# Status_LEDs.net
KiCad netlist of a schematic drawn in Altium Designer
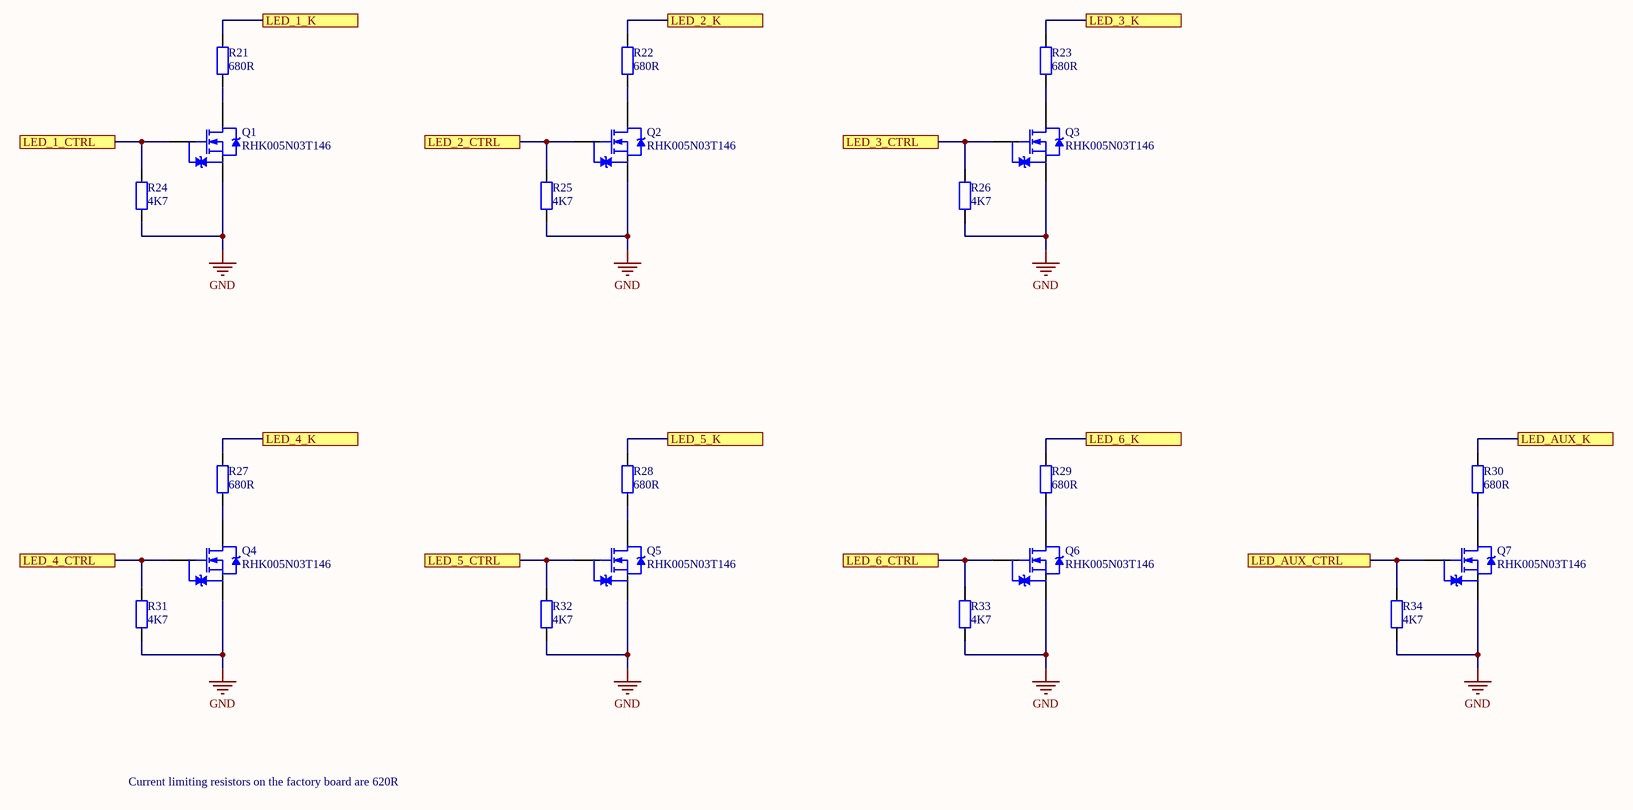
[diagram p0: Status LEDs.SchDoc]

(export (version "E")
  (design (tool "Eeschema 10.0.6"))
  (components
    (comp (ref "Q1")
      (value "RHK005N03T146")
      (footprint "RHK005N03T146 - SOT95P280X110-3N")
      (description "MOSFET N-CH 30V 500MA")
      (libsource (lib "KBuchka-IntLib") (part "RHK005N03T146"))
    )
    (comp (ref "Q2")
      (value "RHK005N03T146")
      (footprint "RHK005N03T146 - SOT95P280X110-3N")
      (description "MOSFET N-CH 30V 500MA")
      (libsource (lib "KBuchka-IntLib") (part "RHK005N03T146"))
    )
    (comp (ref "Q3")
      (value "RHK005N03T146")
      (footprint "RHK005N03T146 - SOT95P280X110-3N")
      (description "MOSFET N-CH 30V 500MA")
      (libsource (lib "KBuchka-IntLib") (part "RHK005N03T146"))
    )
    (comp (ref "Q4")
      (value "RHK005N03T146")
      (footprint "RHK005N03T146 - SOT95P280X110-3N")
      (description "MOSFET N-CH 30V 500MA")
      (libsource (lib "KBuchka-IntLib") (part "RHK005N03T146"))
    )
    (comp (ref "Q5")
      (value "RHK005N03T146")
      (footprint "RHK005N03T146 - SOT95P280X110-3N")
      (description "MOSFET N-CH 30V 500MA")
      (libsource (lib "KBuchka-IntLib") (part "RHK005N03T146"))
    )
    (comp (ref "Q6")
      (value "RHK005N03T146")
      (footprint "RHK005N03T146 - SOT95P280X110-3N")
      (description "MOSFET N-CH 30V 500MA")
      (libsource (lib "KBuchka-IntLib") (part "RHK005N03T146"))
    )
    (comp (ref "Q7")
      (value "RHK005N03T146")
      (footprint "RHK005N03T146 - SOT95P280X110-3N")
      (description "MOSFET N-CH 30V 500MA")
      (libsource (lib "KBuchka-IntLib") (part "RHK005N03T146"))
    )
    (comp (ref "R21")
      (value "680R")
      (footprint "RES_SM0603_YAGEORC_N")
      (description "RES 680R SM0603 YAGEO RC_L")
      (fields
        (field (name "MANUFACTURER") "Yageo")
        (field (name "MANUFACTURER PART NUMBER") "RC0603FR-07680RL")
      )
      (libsource (lib "Yageo") (part "RC0603FR-07680RL"))
    )
    (comp (ref "R22")
      (value "680R")
      (footprint "RES_SM0603_YAGEORC_N")
      (description "RES 680R SM0603 YAGEO RC_L")
      (fields
        (field (name "MANUFACTURER") "Yageo")
        (field (name "MANUFACTURER PART NUMBER") "RC0603FR-07680RL")
      )
      (libsource (lib "Yageo") (part "RC0603FR-07680RL"))
    )
    (comp (ref "R23")
      (value "680R")
      (footprint "RES_SM0603_YAGEORC_N")
      (description "RES 680R SM0603 YAGEO RC_L")
      (fields
        (field (name "MANUFACTURER") "Yageo")
        (field (name "MANUFACTURER PART NUMBER") "RC0603FR-07680RL")
      )
      (libsource (lib "Yageo") (part "RC0603FR-07680RL"))
    )
    (comp (ref "R24")
      (value "4K7")
      (footprint "RES_SM0603_YAGEORC_N")
      (description "RES 4K7 SM0603 YAGEO RC_L")
      (fields
        (field (name "MANUFACTURER") "Yageo")
        (field (name "MANUFACTURER PART NUMBER") "RC0603FR-074K7L")
      )
      (libsource (lib "Yageo") (part "RC0603FR-074K7L"))
    )
    (comp (ref "R25")
      (value "4K7")
      (footprint "RES_SM0603_YAGEORC_N")
      (description "RES 4K7 SM0603 YAGEO RC_L")
      (fields
        (field (name "MANUFACTURER") "Yageo")
        (field (name "MANUFACTURER PART NUMBER") "RC0603FR-074K7L")
      )
      (libsource (lib "Yageo") (part "RC0603FR-074K7L"))
    )
    (comp (ref "R26")
      (value "4K7")
      (footprint "RES_SM0603_YAGEORC_N")
      (description "RES 4K7 SM0603 YAGEO RC_L")
      (fields
        (field (name "MANUFACTURER") "Yageo")
        (field (name "MANUFACTURER PART NUMBER") "RC0603FR-074K7L")
      )
      (libsource (lib "Yageo") (part "RC0603FR-074K7L"))
    )
    (comp (ref "R27")
      (value "680R")
      (footprint "RES_SM0603_YAGEORC_N")
      (description "RES 680R SM0603 YAGEO RC_L")
      (fields
        (field (name "MANUFACTURER") "Yageo")
        (field (name "MANUFACTURER PART NUMBER") "RC0603FR-07680RL")
      )
      (libsource (lib "Yageo") (part "RC0603FR-07680RL"))
    )
    (comp (ref "R28")
      (value "680R")
      (footprint "RES_SM0603_YAGEORC_N")
      (description "RES 680R SM0603 YAGEO RC_L")
      (fields
        (field (name "MANUFACTURER") "Yageo")
        (field (name "MANUFACTURER PART NUMBER") "RC0603FR-07680RL")
      )
      (libsource (lib "Yageo") (part "RC0603FR-07680RL"))
    )
    (comp (ref "R29")
      (value "680R")
      (footprint "RES_SM0603_YAGEORC_N")
      (description "RES 680R SM0603 YAGEO RC_L")
      (fields
        (field (name "MANUFACTURER") "Yageo")
        (field (name "MANUFACTURER PART NUMBER") "RC0603FR-07680RL")
      )
      (libsource (lib "Yageo") (part "RC0603FR-07680RL"))
    )
    (comp (ref "R30")
      (value "680R")
      (footprint "RES_SM0603_YAGEORC_N")
      (description "RES 680R SM0603 YAGEO RC_L")
      (fields
        (field (name "MANUFACTURER") "Yageo")
        (field (name "MANUFACTURER PART NUMBER") "RC0603FR-07680RL")
      )
      (libsource (lib "Yageo") (part "RC0603FR-07680RL"))
    )
    (comp (ref "R31")
      (value "4K7")
      (footprint "RES_SM0603_YAGEORC_N")
      (description "RES 4K7 SM0603 YAGEO RC_L")
      (fields
        (field (name "MANUFACTURER") "Yageo")
        (field (name "MANUFACTURER PART NUMBER") "RC0603FR-074K7L")
      )
      (libsource (lib "Yageo") (part "RC0603FR-074K7L"))
    )
    (comp (ref "R32")
      (value "4K7")
      (footprint "RES_SM0603_YAGEORC_N")
      (description "RES 4K7 SM0603 YAGEO RC_L")
      (fields
        (field (name "MANUFACTURER") "Yageo")
        (field (name "MANUFACTURER PART NUMBER") "RC0603FR-074K7L")
      )
      (libsource (lib "Yageo") (part "RC0603FR-074K7L"))
    )
    (comp (ref "R33")
      (value "4K7")
      (footprint "RES_SM0603_YAGEORC_N")
      (description "RES 4K7 SM0603 YAGEO RC_L")
      (fields
        (field (name "MANUFACTURER") "Yageo")
        (field (name "MANUFACTURER PART NUMBER") "RC0603FR-074K7L")
      )
      (libsource (lib "Yageo") (part "RC0603FR-074K7L"))
    )
    (comp (ref "R34")
      (value "4K7")
      (footprint "RES_SM0603_YAGEORC_N")
      (description "RES 4K7 SM0603 YAGEO RC_L")
      (fields
        (field (name "MANUFACTURER") "Yageo")
        (field (name "MANUFACTURER PART NUMBER") "RC0603FR-074K7L")
      )
      (libsource (lib "Yageo") (part "RC0603FR-074K7L"))
    )
  )
  (nets
    (net (code "1") (name "/LED_1_CTRL") (class "Default")
      (node (ref "Q1") (pin "2") (pinfunction "G_2") (pintype "passive"))
      (node (ref "R24") (pin "2") (pintype "passive"))
    )
    (net (code "2") (name "/LED_1_K") (class "Default") (node (ref "R21") (pin "2") (pintype "passive")))
    (net (code "3") (name "/LED_2_CTRL") (class "Default")
      (node (ref "Q2") (pin "2") (pinfunction "G_2") (pintype "passive"))
      (node (ref "R25") (pin "2") (pintype "passive"))
    )
    (net (code "4") (name "/LED_2_K") (class "Default") (node (ref "R22") (pin "2") (pintype "passive")))
    (net (code "5") (name "/LED_3_CTRL") (class "Default")
      (node (ref "Q3") (pin "2") (pinfunction "G_2") (pintype "passive"))
      (node (ref "R26") (pin "2") (pintype "passive"))
    )
    (net (code "6") (name "/LED_3_K") (class "Default") (node (ref "R23") (pin "2") (pintype "passive")))
    (net (code "7") (name "/LED_4_CTRL") (class "Default")
      (node (ref "Q4") (pin "2") (pinfunction "G_2") (pintype "passive"))
      (node (ref "R31") (pin "2") (pintype "passive"))
    )
    (net (code "8") (name "/LED_4_K") (class "Default") (node (ref "R27") (pin "2") (pintype "passive")))
    (net (code "9") (name "/LED_5_CTRL") (class "Default")
      (node (ref "Q5") (pin "2") (pinfunction "G_2") (pintype "passive"))
      (node (ref "R32") (pin "2") (pintype "passive"))
    )
    (net (code "10") (name "/LED_5_K") (class "Default") (node (ref "R28") (pin "2") (pintype "passive")))
    (net (code "11") (name "/LED_6_CTRL") (class "Default")
      (node (ref "Q6") (pin "2") (pinfunction "G_2") (pintype "passive"))
      (node (ref "R33") (pin "2") (pintype "passive"))
    )
    (net (code "12") (name "/LED_6_K") (class "Default") (node (ref "R29") (pin "2") (pintype "passive")))
    (net (code "13") (name "/LED_AUX_CTRL") (class "Default")
      (node (ref "Q7") (pin "2") (pinfunction "G_2") (pintype "passive"))
      (node (ref "R34") (pin "2") (pintype "passive"))
    )
    (net (code "14") (name "/LED_AUX_K") (class "Default") (node (ref "R30") (pin "2") (pintype "passive")))
    (net (code "15") (name "GND") (class "Default")
      (node (ref "Q1") (pin "1") (pinfunction "S_1") (pintype "passive"))
      (node (ref "Q2") (pin "1") (pinfunction "S_1") (pintype "passive"))
      (node (ref "Q3") (pin "1") (pinfunction "S_1") (pintype "passive"))
      (node (ref "Q4") (pin "1") (pinfunction "S_1") (pintype "passive"))
      (node (ref "Q5") (pin "1") (pinfunction "S_1") (pintype "passive"))
      (node (ref "Q6") (pin "1") (pinfunction "S_1") (pintype "passive"))
      (node (ref "Q7") (pin "1") (pinfunction "S_1") (pintype "passive"))
      (node (ref "R24") (pin "1") (pintype "passive"))
      (node (ref "R25") (pin "1") (pintype "passive"))
      (node (ref "R26") (pin "1") (pintype "passive"))
      (node (ref "R31") (pin "1") (pintype "passive"))
      (node (ref "R32") (pin "1") (pintype "passive"))
      (node (ref "R33") (pin "1") (pintype "passive"))
      (node (ref "R34") (pin "1") (pintype "passive"))
    )
    (net (code "16") (name "Net-(Q1-D)") (class "Default")
      (node (ref "Q1") (pin "3") (pinfunction "D_3") (pintype "passive"))
      (node (ref "R21") (pin "1") (pintype "passive"))
    )
    (net (code "17") (name "Net-(Q2-D)") (class "Default")
      (node (ref "Q2") (pin "3") (pinfunction "D_3") (pintype "passive"))
      (node (ref "R22") (pin "1") (pintype "passive"))
    )
    (net (code "18") (name "Net-(Q3-D)") (class "Default")
      (node (ref "Q3") (pin "3") (pinfunction "D_3") (pintype "passive"))
      (node (ref "R23") (pin "1") (pintype "passive"))
    )
    (net (code "19") (name "Net-(Q4-D)") (class "Default")
      (node (ref "Q4") (pin "3") (pinfunction "D_3") (pintype "passive"))
      (node (ref "R27") (pin "1") (pintype "passive"))
    )
    (net (code "20") (name "Net-(Q5-D)") (class "Default")
      (node (ref "Q5") (pin "3") (pinfunction "D_3") (pintype "passive"))
      (node (ref "R28") (pin "1") (pintype "passive"))
    )
    (net (code "21") (name "Net-(Q6-D)") (class "Default")
      (node (ref "Q6") (pin "3") (pinfunction "D_3") (pintype "passive"))
      (node (ref "R29") (pin "1") (pintype "passive"))
    )
    (net (code "22") (name "Net-(Q7-D)") (class "Default")
      (node (ref "Q7") (pin "3") (pinfunction "D_3") (pintype "passive"))
      (node (ref "R30") (pin "1") (pintype "passive"))
    )
  )
)
